# Planar_HB_3.net
KiCad netlist of a schematic drawn in Altium Designer
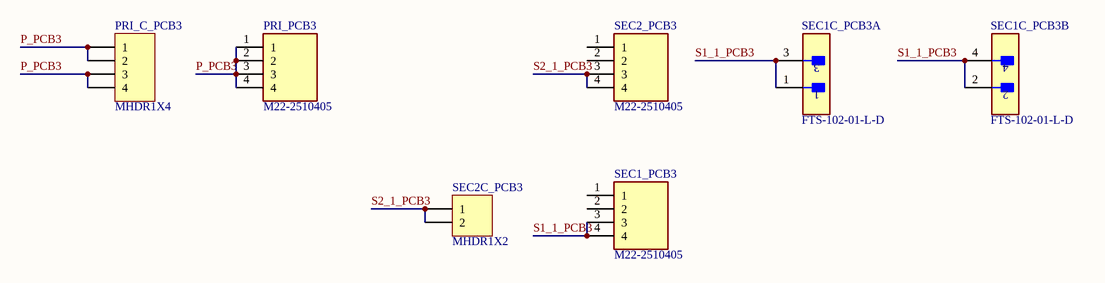
[diagram p0: Planar_HB_3.SchDoc]

(export (version "E")
  (design (tool "Eeschema 10.0.6"))
  (components
    (comp (ref "PRI_C_PCB3")
      (value "MHDR1X4")
      (footprint "MHDR1X4")
      (description "Header, 4-Pin")
      (fields (field (name "PUBLISHER") "Altium Limited"))
      (libsource (lib "Miscellaneous Connectors") (part "MHDR1X4"))
    )
    (comp (ref "PRI_PCB3")
      (value "M22-2510405")
      (footprint "SamacSys:HDRV4W50P0X200_1X4_800X200X525P")
      (description "Connector")
      (fields (field (name "MOUSER PART NUMBER") "855-M22-2510405"))
      (libsource (lib "*") (part "M22-2510405"))
    )
    (comp (ref "SEC1C_PCB3")
      (value "FTS-102-01-L-D")
      (footprint "FP-FTS-102-01-L-D-MFG")
      (description "CONN HEADER VERT 4POS 1.27MM")
      (libsource (lib "Altium Content Vault") (part "1621473add15499e993d6bbd36d0f06"))
    )
    (comp (ref "SEC1_PCB3")
      (value "M22-2510405")
      (footprint "SamacSys:HDRV4W50P0X200_1X4_800X200X525P")
      (description "Connector")
      (fields (field (name "MOUSER PART NUMBER") "855-M22-2510405"))
      (libsource (lib "*") (part "M22-2510405"))
    )
    (comp (ref "SEC2C_PCB3")
      (value "MHDR1X2")
      (footprint "MHDR1X2")
      (description "Header, 2-Pin")
      (fields (field (name "PUBLISHER") "Altium Limited"))
      (libsource (lib "Miscellaneous Connectors") (part "MHDR1X2"))
    )
    (comp (ref "SEC2_PCB3")
      (value "M22-2510405")
      (footprint "SamacSys:HDRV4W50P0X200_1X4_800X200X525P")
      (description "Connector")
      (fields (field (name "MOUSER PART NUMBER") "855-M22-2510405"))
      (libsource (lib "*") (part "M22-2510405"))
    )
  )
  (nets
    (net (code "1") (name "/P_PCB3") (class "Default")
      (node (ref "PRI_C_PCB3") (pin "1") (pinfunction "1_1") (pintype "passive"))
      (node (ref "PRI_C_PCB3") (pin "2") (pinfunction "2_2") (pintype "passive"))
      (node (ref "PRI_C_PCB3") (pin "3") (pinfunction "3_3") (pintype "passive"))
      (node (ref "PRI_C_PCB3") (pin "4") (pinfunction "4_4") (pintype "passive"))
      (node (ref "PRI_PCB3") (pin "1") (pinfunction "1_1") (pintype "passive"))
      (node (ref "PRI_PCB3") (pin "2") (pinfunction "2_2") (pintype "passive"))
      (node (ref "PRI_PCB3") (pin "3") (pinfunction "3_3") (pintype "passive"))
      (node (ref "PRI_PCB3") (pin "4") (pinfunction "4_4") (pintype "passive"))
    )
    (net (code "2") (name "/S1_1_PCB3") (class "Default")
      (node (ref "SEC1C_PCB3") (pin "1") (pinfunction "1_1") (pintype "passive"))
      (node (ref "SEC1C_PCB3") (pin "2") (pinfunction "2_2") (pintype "passive"))
      (node (ref "SEC1C_PCB3") (pin "3") (pinfunction "3_3") (pintype "passive"))
      (node (ref "SEC1C_PCB3") (pin "4") (pinfunction "4_4") (pintype "passive"))
      (node (ref "SEC1_PCB3") (pin "3") (pinfunction "3_3") (pintype "passive"))
      (node (ref "SEC1_PCB3") (pin "4") (pinfunction "4_4") (pintype "passive"))
    )
    (net (code "3") (name "/S2_1_PCB3") (class "Default")
      (node (ref "SEC2C_PCB3") (pin "1") (pinfunction "1_1") (pintype "passive"))
      (node (ref "SEC2C_PCB3") (pin "2") (pinfunction "2_2") (pintype "passive"))
      (node (ref "SEC2_PCB3") (pin "3") (pinfunction "3_3") (pintype "passive"))
      (node (ref "SEC2_PCB3") (pin "4") (pinfunction "4_4") (pintype "passive"))
    )
    (net (code "4") (name "unconnected-(SEC1_PCB3-Pad1)") (class "Default")
      (node (ref "SEC1_PCB3") (pin "1") (pinfunction "1_1") (pintype "passive"))
    )
    (net (code "5") (name "unconnected-(SEC1_PCB3-Pad2)") (class "Default")
      (node (ref "SEC1_PCB3") (pin "2") (pinfunction "2_2") (pintype "passive"))
    )
    (net (code "6") (name "unconnected-(SEC2_PCB3-Pad1)") (class "Default")
      (node (ref "SEC2_PCB3") (pin "1") (pinfunction "1_1") (pintype "passive"))
    )
    (net (code "7") (name "unconnected-(SEC2_PCB3-Pad2)") (class "Default")
      (node (ref "SEC2_PCB3") (pin "2") (pinfunction "2_2") (pintype "passive"))
    )
  )
)
